# TopLevelSchem.net
KiCad netlist of a schematic drawn in Altium Designer
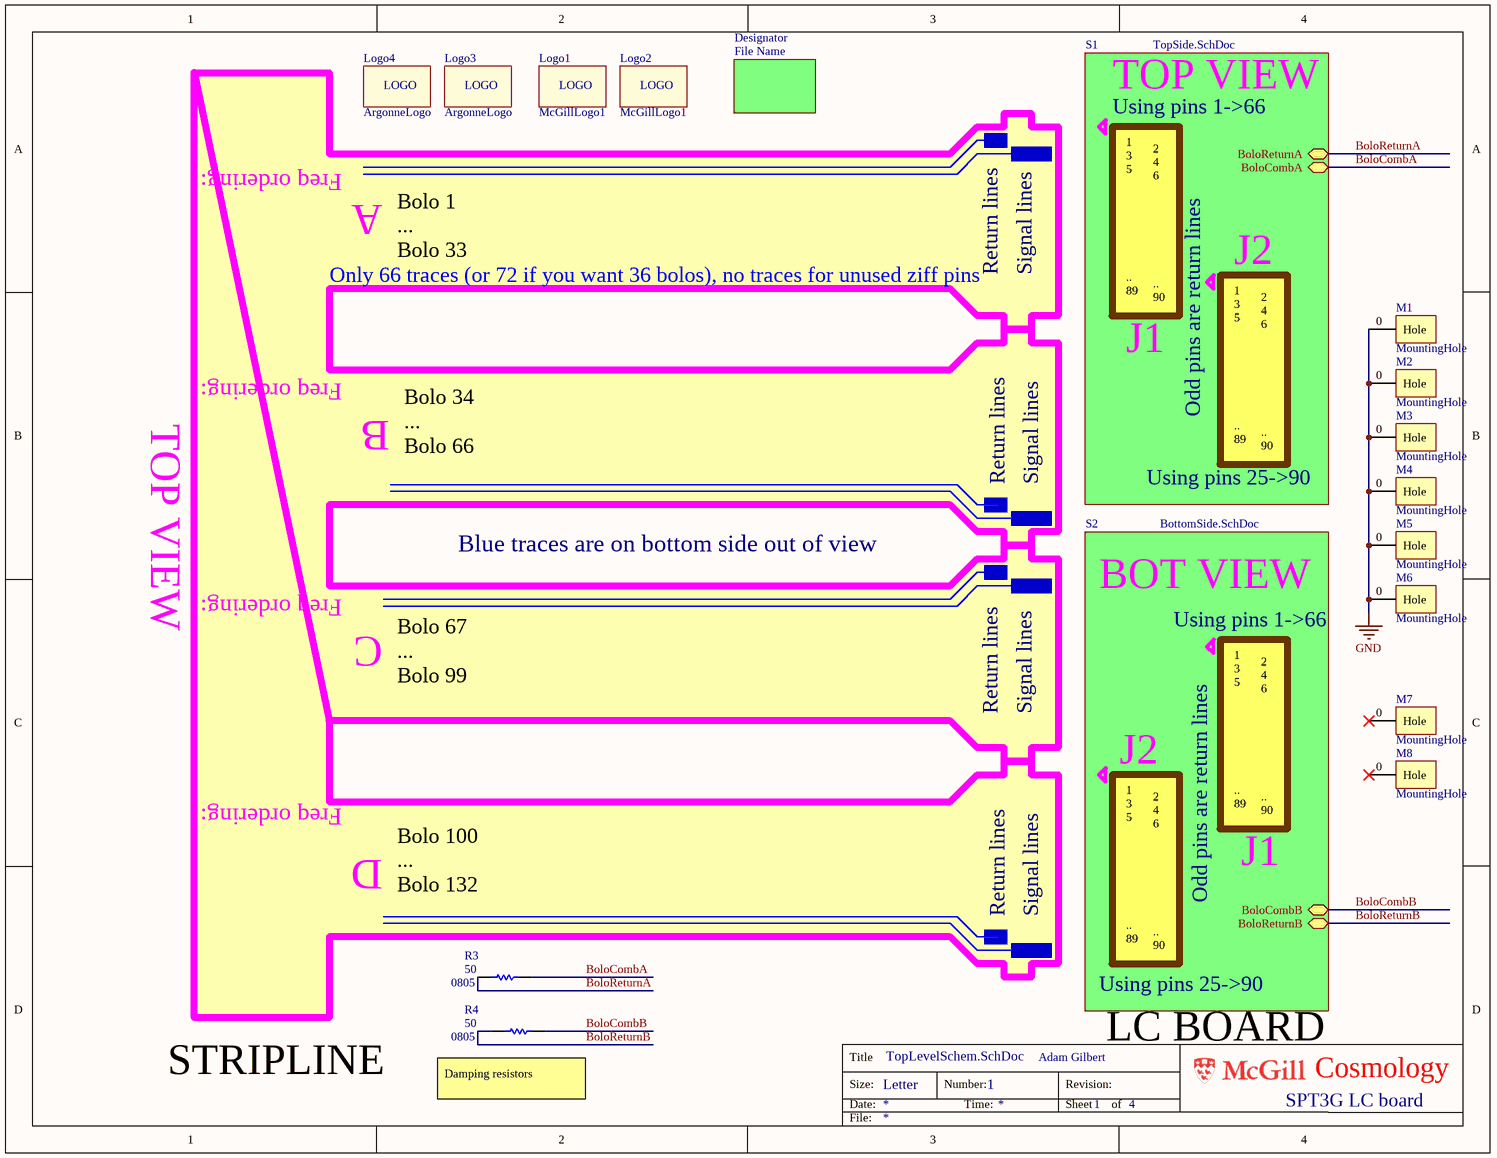
[diagram p0: TopLevelSchem.SchDoc]

(export (version "E")
  (design (tool "Eeschema 10.0.6"))
  (components
    (comp (ref "Logo1")
      (value "McGillLogo1")
      (footprint "McGillLogo1")
      (libsource (lib "SPT3G_LCBoard") (part "Logo"))
    )
    (comp (ref "Logo2")
      (value "McGillLogo1")
      (footprint "McGillLogo1")
      (libsource (lib "SPT3G_LCBoard") (part "Logo"))
    )
    (comp (ref "Logo3")
      (value "ArgonneLogo")
      (footprint "ArgonneLogo")
      (libsource (lib "SPT3G_AdapterBoard") (part "Logo"))
    )
    (comp (ref "Logo4")
      (value "ArgonneLogo")
      (footprint "ArgonneLogo")
      (libsource (lib "SPT3G_AdapterBoard") (part "Logo"))
    )
    (comp (ref "M1")
      (value "MountingHole")
      (footprint "MountingHole")
      (libsource (lib "SPT3G_LCBoard") (part "MountingHole"))
    )
    (comp (ref "M2")
      (value "MountingHole")
      (footprint "MountingHole")
      (libsource (lib "SPT3G_LCBoard") (part "MountingHole"))
    )
    (comp (ref "M3")
      (value "MountingHole")
      (footprint "MountingHole")
      (libsource (lib "SPT3G_LCBoard") (part "MountingHole"))
    )
    (comp (ref "M4")
      (value "MountingHole")
      (footprint "MountingHole")
      (libsource (lib "SPT3G_LCBoard") (part "MountingHole"))
    )
    (comp (ref "M5")
      (value "MountingHole")
      (footprint "MountingHole")
      (libsource (lib "SPT3G_LCBoard") (part "MountingHole"))
    )
    (comp (ref "M6")
      (value "MountingHole")
      (footprint "MountingHole")
      (libsource (lib "SPT3G_LCBoard") (part "MountingHole"))
    )
    (comp (ref "M7")
      (value "MountingHole")
      (footprint "MountingHole")
      (libsource (lib "SPT3G_LCBoard") (part "MountingHole"))
    )
    (comp (ref "M8")
      (value "MountingHole")
      (footprint "MountingHole")
      (libsource (lib "SPT3G_LCBoard") (part "MountingHole"))
    )
    (comp (ref "R3")
      (value "50")
      (footprint "0805")
      (description "Resistor")
      (libsource (lib "SPT3G_LCBoard") (part "Res1206"))
    )
    (comp (ref "R4")
      (value "50")
      (footprint "0805")
      (description "Resistor")
      (libsource (lib "SPT3G_LCBoard") (part "Res1206"))
    )
  )
  (nets
    (net (code "1") (name "/BoloCombA") (class "Default")
      (node (ref "R3") (pin "1") (pinfunction "1_1") (pintype "passive"))
    )
    (net (code "2") (name "/BoloCombB") (class "Default")
      (node (ref "R4") (pin "1") (pinfunction "1_1") (pintype "passive"))
    )
    (net (code "3") (name "/BoloReturnA") (class "Default")
      (node (ref "R3") (pin "2") (pinfunction "2_2") (pintype "passive"))
    )
    (net (code "4") (name "/BoloReturnB") (class "Default")
      (node (ref "R4") (pin "2") (pinfunction "2_2") (pintype "passive"))
    )
    (net (code "5") (name "GND") (class "Default")
      (node (ref "M1") (pin "0") (pinfunction "Hole_0") (pintype "passive"))
      (node (ref "M2") (pin "0") (pinfunction "Hole_0") (pintype "passive"))
      (node (ref "M3") (pin "0") (pinfunction "Hole_0") (pintype "passive"))
      (node (ref "M4") (pin "0") (pinfunction "Hole_0") (pintype "passive"))
      (node (ref "M5") (pin "0") (pinfunction "Hole_0") (pintype "passive"))
      (node (ref "M6") (pin "0") (pinfunction "Hole_0") (pintype "passive"))
    )
    (net (code "6") (name "unconnected-(M7-Hole-Pad0)") (class "Default")
      (node (ref "M7") (pin "0") (pinfunction "Hole_0") (pintype "passive+no_connect"))
    )
    (net (code "7") (name "unconnected-(M8-Hole-Pad0)") (class "Default")
      (node (ref "M8") (pin "0") (pinfunction "Hole_0") (pintype "passive+no_connect"))
    )
  )
)
